# connectors.net
KiCad netlist of a schematic drawn in Altium Designer
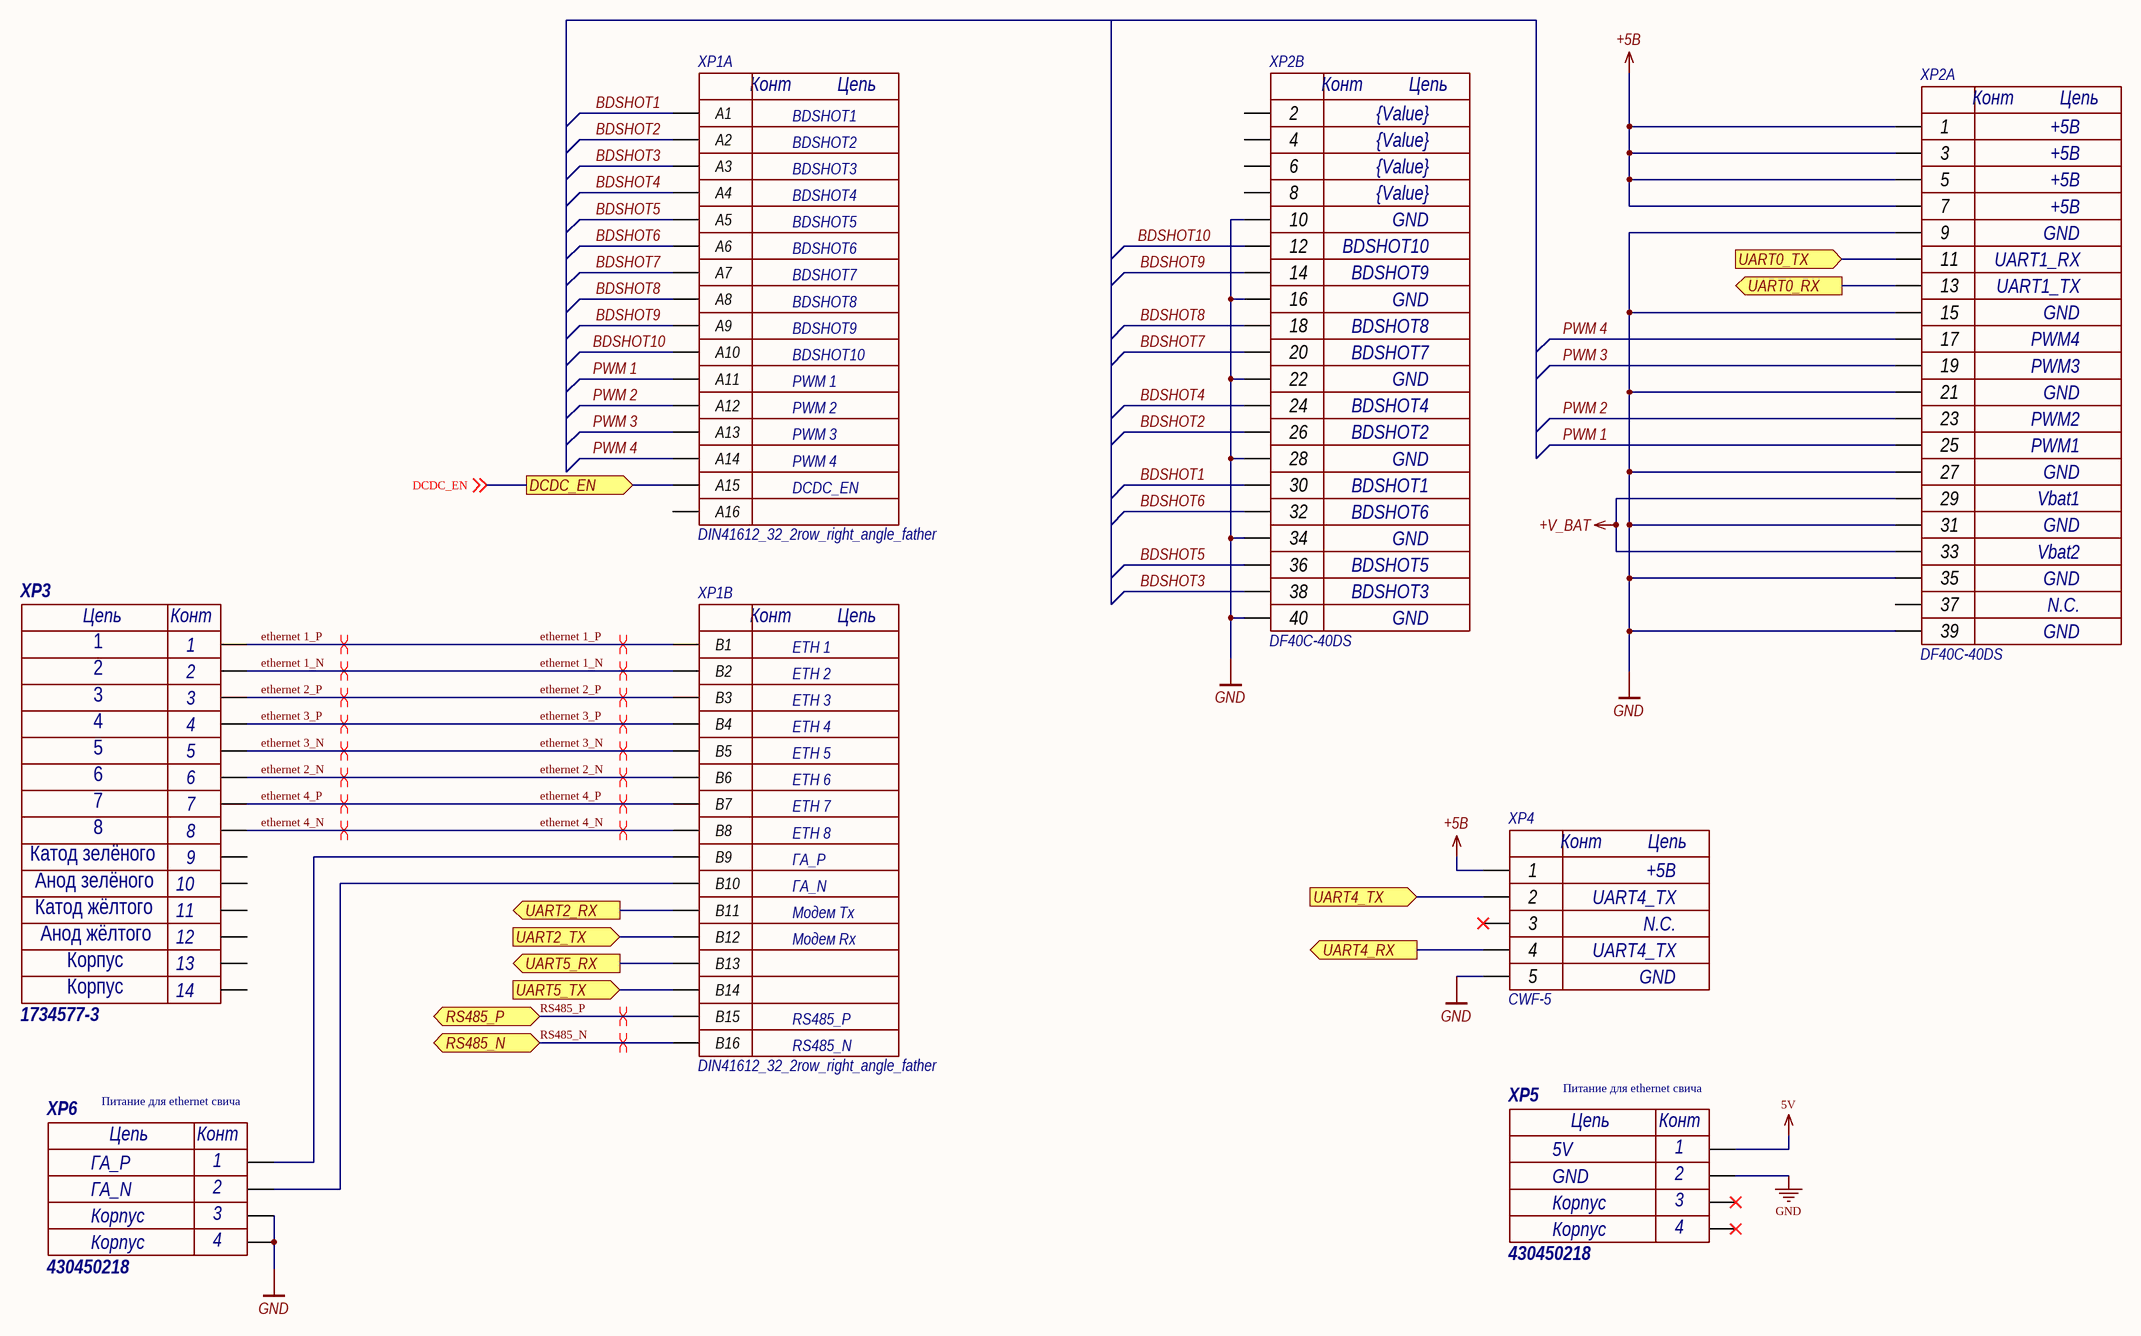
[diagram p0: connectors.SchDoc]

(export (version "E")
  (design (tool "Eeschema 10.0.6"))
  (components
    (comp (ref "XP1")
      (value "DIN41612_32_2row_right_angle_father")
      (footprint "DIN41612_32_2row_right_angle_father")
      (libsource (lib "Hydrolib") (part "DIN41612_32_2row"))
    )
    (comp (ref "XP2")
      (value "DF40C-40DS")
      (footprint "DF40C-40DS")
      (description "Разъем плата-плата 40 пинов, папа, шаг 0.4мм")
      (fields
        (field (name "VALUE17") "Vbat2")
        (field (name "VALUE20") "GND")
        (field (name "VALUE19") "N.C.")
        (field (name "VALUE18") "GND")
        (field (name "VALUE16") "GND")
        (field (name "VALUE15") "Vbat1")
        (field (name "VALUE14") "GND")
        (field (name "VALUE13") "PWM1")
        (field (name "VALUE12") "PWM2")
        (field (name "VALUE11") "GND")
        (field (name "VALUE10") "PWM3")
        (field (name "VALUE9") "PWM4")
        (field (name "VALUE8") "GND")
        (field (name "VALUE7") "UART1_TX")
        (field (name "VALUE6") "UART1_RX")
        (field (name "VALUE5") "GND")
        (field (name "VALUE4") "+5В")
        (field (name "VALUE3") "+5В")
        (field (name "VALUE2") "+5В")
        (field (name "VALUE1") "+5В")
      )
      (libsource (lib "Hydrolib") (part "Conn_40pin_double"))
    )
    (comp (ref "XP3")
      (value "1734577-3")
      (footprint "1-1734577-3-rj45-8p8c")
      (description "Модульный разъем, Cat3, RJ45, Гнездо, 8 контакт(-ов), 8 вывод(-ов), 1 порт(-ов)")
      (fields (field (name "PART NUMBER") "1-1734577-3-rj45-8p8c"))
      (libsource (lib "Hydrolib") (part "1-1734577-3-rj45-8p8c"))
    )
    (comp (ref "XP4")
      (value "CWF-5")
      (footprint "CWF-5")
      (description "5-пиновый разъем с ключом")
      (fields
        (field (name "VALUE1") "+5В")
        (field (name "VALUE2") "UART4_TX")
        (field (name "VALUE3") "N.C.")
        (field (name "VALUE4") "UART4_TX")
        (field (name "VALUE5") "GND")
      )
      (libsource (lib "Hydrolib") (part "Conn_5pin"))
    )
    (comp (ref "XP5")
      (value "430450218")
      (footprint "Molex_430450218")
      (fields
        (field (name "VALUE3") "Корпус")
        (field (name "VALUE2") "GND")
        (field (name "VALUE4") "Корпус")
        (field (name "VALUE1") "5V")
        (field (name "PART NUMBER") "Molex_430450218")
        (field (name "PARAMETER 1") "Питание для ethernet свича")
      )
      (libsource (lib "Hydrolib") (part "Molex_430450218"))
    )
    (comp (ref "XP6")
      (value "430450218")
      (footprint "Molex_430450218")
      (fields
        (field (name "VALUE3") "Корпус")
        (field (name "VALUE2") "ГА_N")
        (field (name "VALUE4") "Корпус")
        (field (name "VALUE1") "ГА_P")
        (field (name "PART NUMBER") "Molex_430450218")
        (field (name "PARAMETER 1") "Питание для ethernet свича")
      )
      (libsource (lib "Hydrolib") (part "Molex_430450218"))
    )
  )
  (nets
    (net (code "1") (name "+5В") (class "Default")
      (node (ref "XP2") (pin "1") (pinfunction "1_1") (pintype "passive"))
      (node (ref "XP2") (pin "3") (pinfunction "3_3") (pintype "passive"))
      (node (ref "XP2") (pin "5") (pinfunction "5_5") (pintype "passive"))
      (node (ref "XP2") (pin "7") (pinfunction "7_7") (pintype "passive"))
      (node (ref "XP4") (pin "1") (pinfunction "1_1") (pintype "passive"))
    )
    (net (code "2") (name "+V_BAT") (class "Default")
      (node (ref "XP2") (pin "29") (pinfunction "29_29") (pintype "passive"))
      (node (ref "XP2") (pin "33") (pinfunction "33_33") (pintype "passive"))
    )
    (net (code "3") (name "/BDSHOT1") (class "Default")
      (node (ref "XP1") (pin "A1") (pinfunction "A1_A1") (pintype "passive"))
      (node (ref "XP2") (pin "30") (pinfunction "30_30") (pintype "passive"))
    )
    (net (code "4") (name "/BDSHOT2") (class "Default")
      (node (ref "XP1") (pin "A2") (pinfunction "A2_A2") (pintype "passive"))
      (node (ref "XP2") (pin "26") (pinfunction "26_26") (pintype "passive"))
    )
    (net (code "5") (name "/BDSHOT3") (class "Default")
      (node (ref "XP1") (pin "A3") (pinfunction "A3_A3") (pintype "passive"))
      (node (ref "XP2") (pin "38") (pinfunction "38_38") (pintype "passive"))
    )
    (net (code "6") (name "/BDSHOT4") (class "Default")
      (node (ref "XP1") (pin "A4") (pinfunction "A4_A4") (pintype "passive"))
      (node (ref "XP2") (pin "24") (pinfunction "24_24") (pintype "passive"))
    )
    (net (code "7") (name "/BDSHOT5") (class "Default")
      (node (ref "XP1") (pin "A5") (pinfunction "A5_A5") (pintype "passive"))
      (node (ref "XP2") (pin "36") (pinfunction "36_36") (pintype "passive"))
    )
    (net (code "8") (name "/BDSHOT6") (class "Default")
      (node (ref "XP1") (pin "A6") (pinfunction "A6_A6") (pintype "passive"))
      (node (ref "XP2") (pin "32") (pinfunction "32_32") (pintype "passive"))
    )
    (net (code "9") (name "/BDSHOT7") (class "Default")
      (node (ref "XP1") (pin "A7") (pinfunction "A7_A7") (pintype "passive"))
      (node (ref "XP2") (pin "20") (pinfunction "20_20") (pintype "passive"))
    )
    (net (code "10") (name "/BDSHOT8") (class "Default")
      (node (ref "XP1") (pin "A8") (pinfunction "A8_A8") (pintype "passive"))
      (node (ref "XP2") (pin "18") (pinfunction "18_18") (pintype "passive"))
    )
    (net (code "11") (name "/BDSHOT9") (class "Default")
      (node (ref "XP1") (pin "A9") (pinfunction "A9_A9") (pintype "passive"))
      (node (ref "XP2") (pin "14") (pinfunction "14_14") (pintype "passive"))
    )
    (net (code "12") (name "/BDSHOT10") (class "Default")
      (node (ref "XP1") (pin "A10") (pinfunction "A10_A10") (pintype "passive"))
      (node (ref "XP2") (pin "12") (pinfunction "12_12") (pintype "passive"))
    )
    (net (code "13") (name "/PWM 1") (class "Default")
      (node (ref "XP1") (pin "A11") (pinfunction "A11_A11") (pintype "passive"))
      (node (ref "XP2") (pin "25") (pinfunction "25_25") (pintype "passive"))
    )
    (net (code "14") (name "/PWM 2") (class "Default")
      (node (ref "XP1") (pin "A12") (pinfunction "A12_A12") (pintype "passive"))
      (node (ref "XP2") (pin "23") (pinfunction "23_23") (pintype "passive"))
    )
    (net (code "15") (name "/PWM 3") (class "Default")
      (node (ref "XP1") (pin "A13") (pinfunction "A13_A13") (pintype "passive"))
      (node (ref "XP2") (pin "19") (pinfunction "19_19") (pintype "passive"))
    )
    (net (code "16") (name "/PWM 4") (class "Default")
      (node (ref "XP1") (pin "A14") (pinfunction "A14_A14") (pintype "passive"))
      (node (ref "XP2") (pin "17") (pinfunction "17_17") (pintype "passive"))
    )
    (net (code "17") (name "/RS485_N") (class "Default")
      (node (ref "XP1") (pin "B16") (pinfunction "B16_B16") (pintype "passive"))
    )
    (net (code "18") (name "/RS485_P") (class "Default")
      (node (ref "XP1") (pin "B15") (pinfunction "B15_B15") (pintype "passive"))
    )
    (net (code "19") (name "/UART0_RX") (class "Default")
      (node (ref "XP2") (pin "13") (pinfunction "13_13") (pintype "passive"))
    )
    (net (code "20") (name "/UART0_TX") (class "Default")
      (node (ref "XP2") (pin "11") (pinfunction "11_11") (pintype "passive"))
    )
    (net (code "21") (name "/UART2_RX") (class "Default")
      (node (ref "XP1") (pin "B11") (pinfunction "B11_B11") (pintype "passive"))
    )
    (net (code "22") (name "/UART2_TX") (class "Default")
      (node (ref "XP1") (pin "B12") (pinfunction "B12_B12") (pintype "passive"))
    )
    (net (code "23") (name "/UART4_RX") (class "Default")
      (node (ref "XP4") (pin "4") (pinfunction "4_4") (pintype "passive"))
    )
    (net (code "24") (name "/UART4_TX") (class "Default")
      (node (ref "XP4") (pin "2") (pinfunction "2_2") (pintype "passive"))
    )
    (net (code "25") (name "/UART5_RX") (class "Default")
      (node (ref "XP1") (pin "B13") (pinfunction "B13_B13") (pintype "passive"))
    )
    (net (code "26") (name "/UART5_TX") (class "Default")
      (node (ref "XP1") (pin "B14") (pinfunction "B14_B14") (pintype "passive"))
    )
    (net (code "27") (name "/ethernet 1_N") (class "Default")
      (node (ref "XP1") (pin "B2") (pinfunction "B2_B2") (pintype "passive"))
      (node (ref "XP3") (pin "2") (pinfunction "2_2") (pintype "passive"))
    )
    (net (code "28") (name "/ethernet 1_P") (class "Default")
      (node (ref "XP1") (pin "B1") (pinfunction "B1_B1") (pintype "passive"))
      (node (ref "XP3") (pin "1") (pinfunction "1_1") (pintype "passive"))
    )
    (net (code "29") (name "/ethernet 2_N") (class "Default")
      (node (ref "XP1") (pin "B6") (pinfunction "B6_B6") (pintype "passive"))
      (node (ref "XP3") (pin "6") (pinfunction "6_6") (pintype "passive"))
    )
    (net (code "30") (name "/ethernet 2_P") (class "Default")
      (node (ref "XP1") (pin "B3") (pinfunction "B3_B3") (pintype "passive"))
      (node (ref "XP3") (pin "3") (pinfunction "3_3") (pintype "passive"))
    )
    (net (code "31") (name "/ethernet 3_N") (class "Default")
      (node (ref "XP1") (pin "B5") (pinfunction "B5_B5") (pintype "passive"))
      (node (ref "XP3") (pin "5") (pinfunction "5_5") (pintype "passive"))
    )
    (net (code "32") (name "/ethernet 3_P") (class "Default")
      (node (ref "XP1") (pin "B4") (pinfunction "B4_B4") (pintype "passive"))
      (node (ref "XP3") (pin "4") (pinfunction "4_4") (pintype "passive"))
    )
    (net (code "33") (name "/ethernet 4_N") (class "Default")
      (node (ref "XP1") (pin "B8") (pinfunction "B8_B8") (pintype "passive"))
      (node (ref "XP3") (pin "8") (pinfunction "8_8") (pintype "passive"))
    )
    (net (code "34") (name "/ethernet 4_P") (class "Default")
      (node (ref "XP1") (pin "B7") (pinfunction "B7_B7") (pintype "passive"))
      (node (ref "XP3") (pin "7") (pinfunction "7_7") (pintype "passive"))
    )
    (net (code "35") (name "5V") (class "Default")
      (node (ref "XP5") (pin "1") (pinfunction "1_1") (pintype "passive"))
    )
    (net (code "36") (name "DCDC_EN") (class "Default")
      (node (ref "XP1") (pin "A15") (pinfunction "A15_A15") (pintype "passive"))
    )
    (net (code "37") (name "GND") (class "Default")
      (node (ref "XP2") (pin "10") (pinfunction "10_10") (pintype "passive"))
      (node (ref "XP2") (pin "15") (pinfunction "15_15") (pintype "passive"))
      (node (ref "XP2") (pin "16") (pinfunction "16_16") (pintype "passive"))
      (node (ref "XP2") (pin "21") (pinfunction "21_21") (pintype "passive"))
      (node (ref "XP2") (pin "22") (pinfunction "22_22") (pintype "passive"))
      (node (ref "XP2") (pin "27") (pinfunction "27_27") (pintype "passive"))
      (node (ref "XP2") (pin "28") (pinfunction "28_28") (pintype "passive"))
      (node (ref "XP2") (pin "31") (pinfunction "31_31") (pintype "passive"))
      (node (ref "XP2") (pin "34") (pinfunction "34_34") (pintype "passive"))
      (node (ref "XP2") (pin "35") (pinfunction "35_35") (pintype "passive"))
      (node (ref "XP2") (pin "39") (pinfunction "39_39") (pintype "passive"))
      (node (ref "XP2") (pin "40") (pinfunction "40_40") (pintype "passive"))
      (node (ref "XP2") (pin "9") (pinfunction "9_9") (pintype "passive"))
      (node (ref "XP4") (pin "5") (pinfunction "5_5") (pintype "passive"))
      (node (ref "XP5") (pin "2") (pinfunction "2_2") (pintype "passive"))
      (node (ref "XP6") (pin "0") (pinfunction "0_0") (pintype "passive"))
    )
    (net (code "38") (name "Net-(XP1-PadB9)") (class "Default")
      (node (ref "XP1") (pin "B9") (pinfunction "B9_B9") (pintype "passive"))
      (node (ref "XP6") (pin "1") (pinfunction "1_1") (pintype "passive"))
    )
    (net (code "39") (name "Net-(XP1-PadB10)") (class "Default")
      (node (ref "XP1") (pin "B10") (pinfunction "B10_B10") (pintype "passive"))
      (node (ref "XP6") (pin "2") (pinfunction "2_2") (pintype "passive"))
    )
    (net (code "40") (name "unconnected-(XP1-PadA16)") (class "Default")
      (node (ref "XP1") (pin "A16") (pinfunction "A16_A16") (pintype "passive"))
    )
    (net (code "41") (name "unconnected-(XP2-Pad2)") (class "Default")
      (node (ref "XP2") (pin "2") (pinfunction "2_2") (pintype "passive"))
    )
    (net (code "42") (name "unconnected-(XP2-Pad4)") (class "Default")
      (node (ref "XP2") (pin "4") (pinfunction "4_4") (pintype "passive"))
    )
    (net (code "43") (name "unconnected-(XP2-Pad6)") (class "Default")
      (node (ref "XP2") (pin "6") (pinfunction "6_6") (pintype "passive"))
    )
    (net (code "44") (name "unconnected-(XP2-Pad8)") (class "Default")
      (node (ref "XP2") (pin "8") (pinfunction "8_8") (pintype "passive"))
    )
    (net (code "45") (name "unconnected-(XP2-Pad37)") (class "Default")
      (node (ref "XP2") (pin "37") (pinfunction "37_37") (pintype "passive"))
    )
    (net (code "46") (name "unconnected-(XP3-Pad9)") (class "Default")
      (node (ref "XP3") (pin "9") (pinfunction "9_9") (pintype "passive"))
    )
    (net (code "47") (name "unconnected-(XP3-Pad10)") (class "Default")
      (node (ref "XP3") (pin "10") (pinfunction "10_10") (pintype "passive"))
    )
    (net (code "48") (name "unconnected-(XP3-Pad11)") (class "Default")
      (node (ref "XP3") (pin "11") (pinfunction "11_11") (pintype "passive"))
    )
    (net (code "49") (name "unconnected-(XP3-Pad12)") (class "Default")
      (node (ref "XP3") (pin "12") (pinfunction "12_12") (pintype "passive"))
    )
    (net (code "50") (name "unconnected-(XP3-PadMH1)") (class "Default")
      (node (ref "XP3") (pin "MH1") (pinfunction "MH1_MH1") (pintype "passive"))
    )
    (net (code "51") (name "unconnected-(XP3-PadMH2)") (class "Default")
      (node (ref "XP3") (pin "MH2") (pinfunction "MH2_MH2") (pintype "passive"))
    )
    (net (code "52") (name "unconnected-(XP4-Pad3)") (class "Default")
      (node (ref "XP4") (pin "3") (pinfunction "3_3") (pintype "passive+no_connect"))
    )
    (net (code "53") (name "unconnected-(XP5-Pad0)") (class "Default")
      (node (ref "XP5") (pin "0") (pinfunction "0_0") (pintype "passive+no_connect"))
    )
    (net (code "54") (name "unconnected-(XP5-Pad0)_1") (class "Default")
      (node (ref "XP5") (pin "0") (pinfunction "0_0") (pintype "passive+no_connect"))
    )
  )
)
